# working.net
KiCad netlist of a schematic drawn in EAGLE
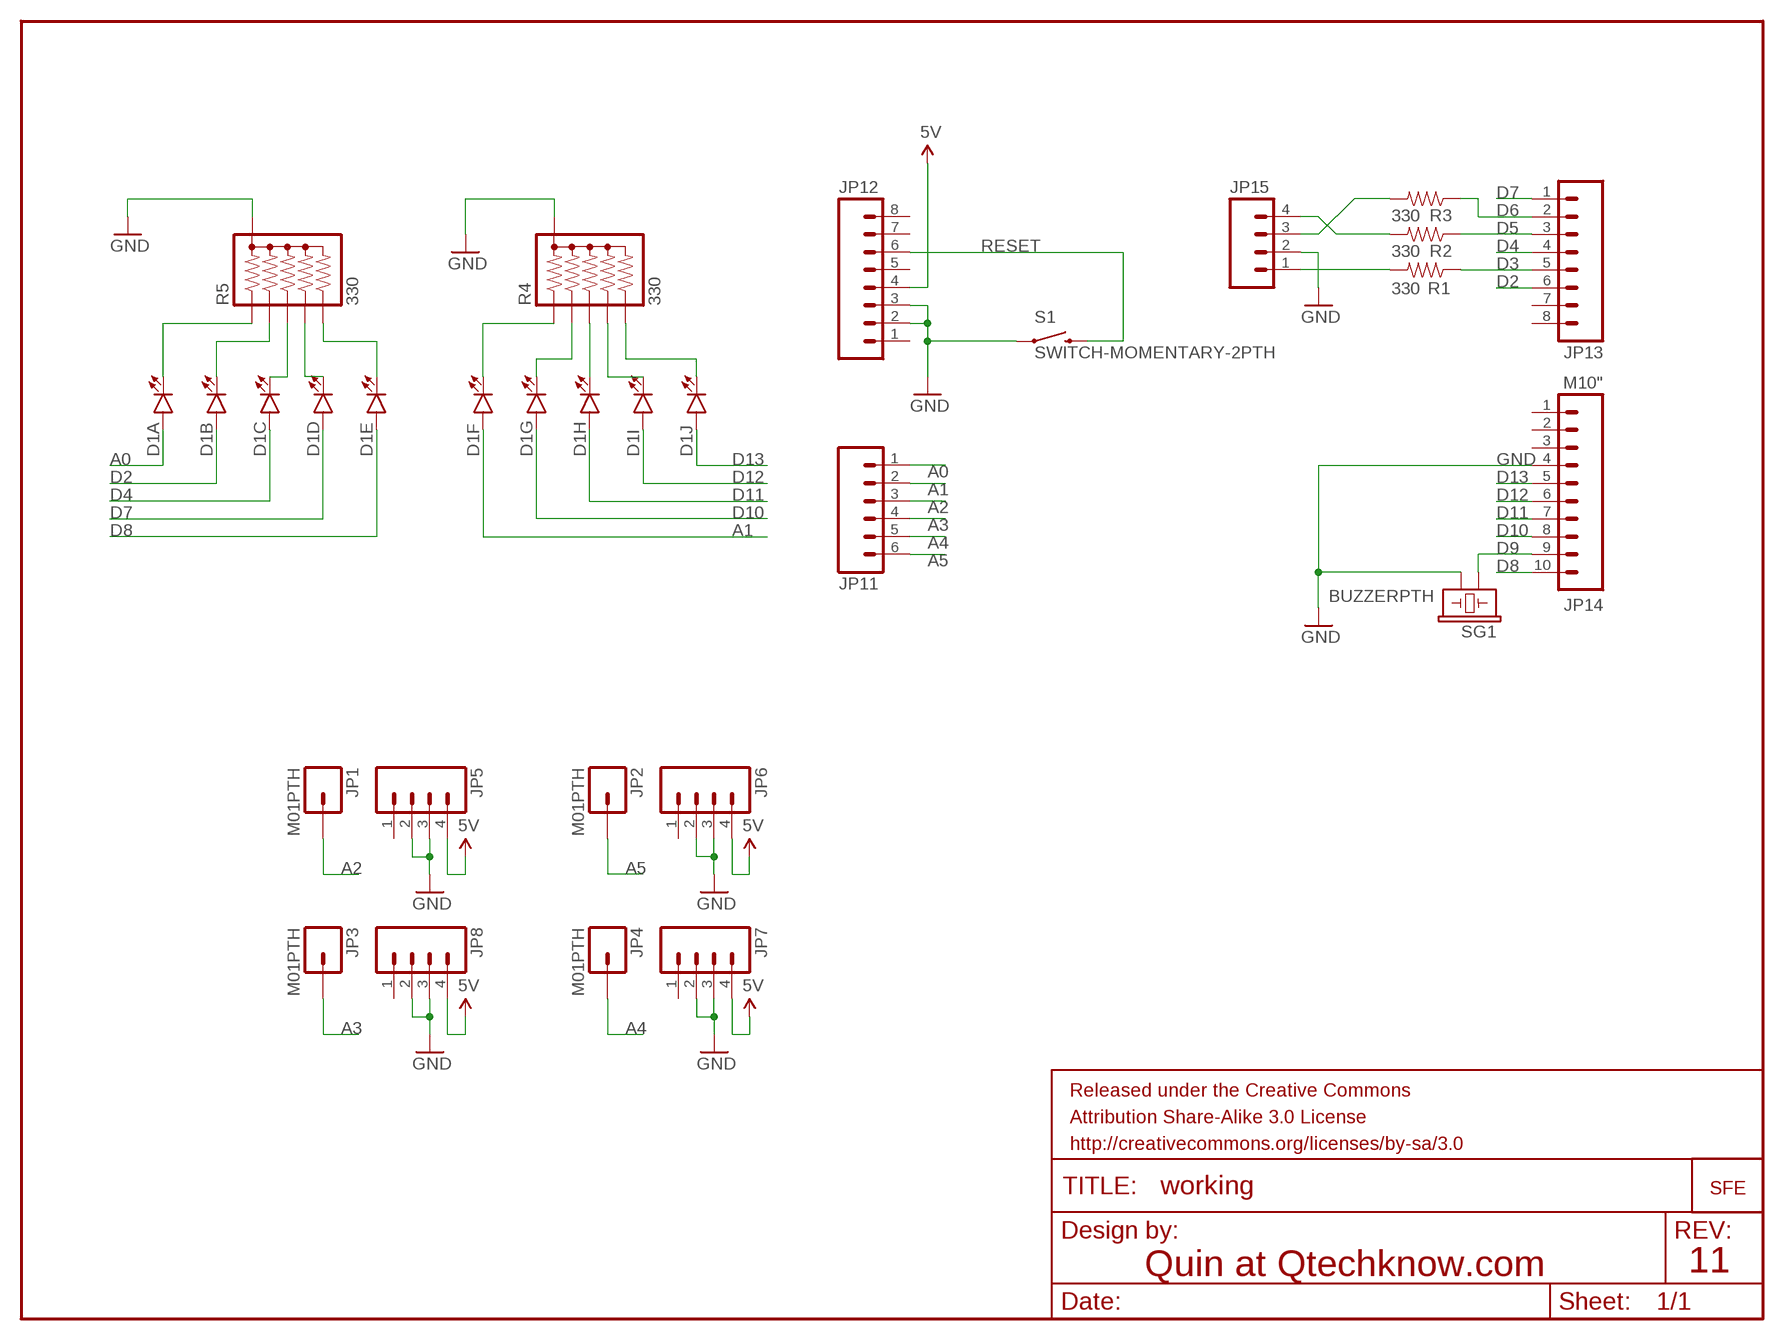
[diagram p0: schematic, sheet 1]

(export (version "E")
  (design (tool "Eeschema 10.0.6"))
  (components
    (comp (ref "D1")
      (value "LED_BARGRAPH_10")
      (footprint "eagle-import:LED_BARGAPH_10")
      (libsource (lib "eagle-import") (part "LED_BARGRAPH_10"))
    )
    (comp (ref "FRAME1")
      (value "FRAME-LETTER")
      (footprint "eagle-import:CREATIVE_COMMONS")
      (libsource (lib "eagle-import") (part "FRAME-LETTER"))
    )
    (comp (ref "JP1")
      (value "M01PTH")
      (footprint "eagle-import:1X01")
      (libsource (lib "eagle-import") (part "M01PTH"))
    )
    (comp (ref "JP2")
      (value "M01PTH")
      (footprint "eagle-import:1X01")
      (libsource (lib "eagle-import") (part "M01PTH"))
    )
    (comp (ref "JP3")
      (value "M01PTH")
      (footprint "eagle-import:1X01")
      (libsource (lib "eagle-import") (part "M01PTH"))
    )
    (comp (ref "JP4")
      (value "M01PTH")
      (footprint "eagle-import:1X01")
      (libsource (lib "eagle-import") (part "M01PTH"))
    )
    (comp (ref "JP5")
      (value "M04PTH")
      (footprint "eagle-import:1X04")
      (libsource (lib "eagle-import") (part "M04PTH"))
    )
    (comp (ref "JP6")
      (value "M04PTH")
      (footprint "eagle-import:1X04")
      (libsource (lib "eagle-import") (part "M04PTH"))
    )
    (comp (ref "JP7")
      (value "M04PTH")
      (footprint "eagle-import:1X04")
      (libsource (lib "eagle-import") (part "M04PTH"))
    )
    (comp (ref "JP8")
      (value "M04PTH")
      (footprint "eagle-import:1X04")
      (libsource (lib "eagle-import") (part "M04PTH"))
    )
    (comp (ref "JP9")
      (value "LOGO-SFENEW")
      (footprint "eagle-import:SFE-NEW-WEBLOGO")
      (libsource (lib "eagle-import") (part "LOGO-SFENEW"))
    )
    (comp (ref "JP11")
      (value "M06SIP")
      (footprint "eagle-import:1X06")
      (libsource (lib "eagle-import") (part "M06SIP"))
    )
    (comp (ref "JP12")
      (value "M081X08")
      (footprint "eagle-import:1X08")
      (libsource (lib "eagle-import") (part "M081X08"))
    )
    (comp (ref "JP13")
      (value "M081X08")
      (footprint "eagle-import:1X08")
      (libsource (lib "eagle-import") (part "M081X08"))
    )
    (comp (ref "JP14")
      (value "M10\"")
      (footprint "eagle-import:1X10")
      (libsource (lib "eagle-import") (part "M10{dblquote}"))
    )
    (comp (ref "JP15")
      (value "M04PTH")
      (footprint "eagle-import:1X04")
      (libsource (lib "eagle-import") (part "M04PTH"))
    )
    (comp (ref "R1")
      (value "330")
      (footprint "eagle-import:1_6W-RES")
      (libsource (lib "eagle-import") (part "RESISTORPTH-1/6W"))
    )
    (comp (ref "R2")
      (value "330")
      (footprint "eagle-import:1_6W-RES")
      (libsource (lib "eagle-import") (part "RESISTORPTH-1/6W"))
    )
    (comp (ref "R3")
      (value "330")
      (footprint "eagle-import:1_6W-RES")
      (libsource (lib "eagle-import") (part "RESISTORPTH-1/6W"))
    )
    (comp (ref "R4")
      (value "330")
      (footprint "eagle-import:RPACK-SIP-PTH-5")
      (libsource (lib "eagle-import") (part "RPACK-BUSSED-SIP-PTH-5"))
    )
    (comp (ref "R5")
      (value "330")
      (footprint "eagle-import:RPACK-SIP-PTH-5")
      (libsource (lib "eagle-import") (part "RPACK-BUSSED-SIP-PTH-5"))
    )
    (comp (ref "S1")
      (value "SWITCH-MOMENTARY-2PTH")
      (footprint "eagle-import:TACTILE-PTH")
      (libsource (lib "eagle-import") (part "SWITCH-MOMENTARY-2PTH"))
    )
    (comp (ref "SG1")
      (value "BUZZERPTH")
      (footprint "eagle-import:BUZZER-12MM")
      (libsource (lib "eagle-import") (part "BUZZERPTH"))
    )
  )
  (nets
    (net (code "1") (name "/A0") (class "Default")
      (node (ref "D1") (pin "1") (pinfunction "A_1") (pintype "passive"))
      (node (ref "JP11") (pin "1") (pinfunction "1_1") (pintype "passive"))
    )
    (net (code "2") (name "/A1") (class "Default")
      (node (ref "D1") (pin "6") (pinfunction "A_6") (pintype "passive"))
      (node (ref "JP11") (pin "2") (pinfunction "2_2") (pintype "passive"))
    )
    (net (code "3") (name "/A2") (class "Default")
      (node (ref "JP1") (pin "1") (pinfunction "1_1") (pintype "passive"))
      (node (ref "JP11") (pin "3") (pinfunction "3_3") (pintype "passive"))
    )
    (net (code "4") (name "/A3") (class "Default")
      (node (ref "JP11") (pin "4") (pinfunction "4_4") (pintype "passive"))
      (node (ref "JP3") (pin "1") (pinfunction "1_1") (pintype "passive"))
    )
    (net (code "5") (name "/A4") (class "Default")
      (node (ref "JP11") (pin "5") (pinfunction "5_5") (pintype "passive"))
      (node (ref "JP4") (pin "1") (pinfunction "1_1") (pintype "passive"))
    )
    (net (code "6") (name "/A5") (class "Default")
      (node (ref "JP11") (pin "6") (pinfunction "6_6") (pintype "passive"))
      (node (ref "JP2") (pin "1") (pinfunction "1_1") (pintype "passive"))
    )
    (net (code "7") (name "/D2") (class "Default")
      (node (ref "D1") (pin "2") (pinfunction "A_2") (pintype "passive"))
      (node (ref "JP13") (pin "6") (pinfunction "6_6") (pintype "passive"))
    )
    (net (code "8") (name "/D3") (class "Default")
      (node (ref "JP13") (pin "5") (pinfunction "5_5") (pintype "passive"))
      (node (ref "R1") (pin "1") (pinfunction "1_1") (pintype "passive"))
    )
    (net (code "9") (name "/D4") (class "Default")
      (node (ref "D1") (pin "3") (pinfunction "A_3") (pintype "passive"))
      (node (ref "JP13") (pin "4") (pinfunction "4_4") (pintype "passive"))
    )
    (net (code "10") (name "/D5") (class "Default")
      (node (ref "JP13") (pin "3") (pinfunction "3_3") (pintype "passive"))
      (node (ref "R2") (pin "1") (pinfunction "1_1") (pintype "passive"))
    )
    (net (code "11") (name "/D6") (class "Default")
      (node (ref "JP13") (pin "2") (pinfunction "2_2") (pintype "passive"))
      (node (ref "R3") (pin "1") (pinfunction "1_1") (pintype "passive"))
    )
    (net (code "12") (name "/D7") (class "Default")
      (node (ref "D1") (pin "4") (pinfunction "A_4") (pintype "passive"))
      (node (ref "JP13") (pin "1") (pinfunction "1_1") (pintype "passive"))
    )
    (net (code "13") (name "/D8") (class "Default")
      (node (ref "D1") (pin "5") (pinfunction "A_5") (pintype "passive"))
      (node (ref "JP14") (pin "10") (pinfunction "10_10") (pintype "passive"))
    )
    (net (code "14") (name "/D9") (class "Default")
      (node (ref "JP14") (pin "9") (pinfunction "9_9") (pintype "passive"))
      (node (ref "SG1") (pin "+") (pinfunction "1_+") (pintype "passive"))
    )
    (net (code "15") (name "/D10") (class "Default")
      (node (ref "D1") (pin "7") (pinfunction "A_7") (pintype "passive"))
      (node (ref "JP14") (pin "8") (pinfunction "8_8") (pintype "passive"))
    )
    (net (code "16") (name "/D11") (class "Default")
      (node (ref "D1") (pin "8") (pinfunction "A_8") (pintype "passive"))
      (node (ref "JP14") (pin "7") (pinfunction "7_7") (pintype "passive"))
    )
    (net (code "17") (name "/D12") (class "Default")
      (node (ref "D1") (pin "9") (pinfunction "A_9") (pintype "passive"))
      (node (ref "JP14") (pin "6") (pinfunction "6_6") (pintype "passive"))
    )
    (net (code "18") (name "/D13") (class "Default")
      (node (ref "D1") (pin "10") (pinfunction "A_10") (pintype "passive"))
      (node (ref "JP14") (pin "5") (pinfunction "5_5") (pintype "passive"))
    )
    (net (code "19") (name "/RESET") (class "Default")
      (node (ref "JP12") (pin "6") (pinfunction "6_6") (pintype "passive"))
      (node (ref "S1") (pin "3") (pinfunction "2_3") (pintype "passive"))
    )
    (net (code "20") (name "5V") (class "Default")
      (node (ref "JP12") (pin "4") (pinfunction "4_4") (pintype "passive"))
      (node (ref "JP5") (pin "4") (pinfunction "4_4") (pintype "passive"))
      (node (ref "JP6") (pin "4") (pinfunction "4_4") (pintype "passive"))
      (node (ref "JP7") (pin "4") (pinfunction "4_4") (pintype "passive"))
      (node (ref "JP8") (pin "4") (pinfunction "4_4") (pintype "passive"))
    )
    (net (code "21") (name "GND") (class "Default")
      (node (ref "JP12") (pin "2") (pinfunction "2_2") (pintype "passive"))
      (node (ref "JP12") (pin "3") (pinfunction "3_3") (pintype "passive"))
      (node (ref "JP14") (pin "4") (pinfunction "4_4") (pintype "passive"))
      (node (ref "JP15") (pin "2") (pinfunction "2_2") (pintype "passive"))
      (node (ref "JP5") (pin "2") (pinfunction "2_2") (pintype "passive"))
      (node (ref "JP5") (pin "3") (pinfunction "3_3") (pintype "passive"))
      (node (ref "JP6") (pin "2") (pinfunction "2_2") (pintype "passive"))
      (node (ref "JP6") (pin "3") (pinfunction "3_3") (pintype "passive"))
      (node (ref "JP7") (pin "2") (pinfunction "2_2") (pintype "passive"))
      (node (ref "JP7") (pin "3") (pinfunction "3_3") (pintype "passive"))
      (node (ref "JP8") (pin "2") (pinfunction "2_2") (pintype "passive"))
      (node (ref "JP8") (pin "3") (pinfunction "3_3") (pintype "passive"))
      (node (ref "R4") (pin "P$1") (pinfunction "1_P$1") (pintype "passive"))
      (node (ref "R5") (pin "P$1") (pinfunction "1_P$1") (pintype "passive"))
      (node (ref "S1") (pin "1") (pinfunction "1_1") (pintype "passive"))
      (node (ref "SG1") (pin "-") (pinfunction "2_-") (pintype "passive"))
    )
    (net (code "22") (name "Net-(D1A-C)") (class "Default")
      (node (ref "D1") (pin "20") (pinfunction "C_20") (pintype "passive"))
      (node (ref "R5") (pin "P$2") (pinfunction "2_P$2") (pintype "passive"))
    )
    (net (code "23") (name "Net-(D1B-C)") (class "Default")
      (node (ref "D1") (pin "19") (pinfunction "C_19") (pintype "passive"))
      (node (ref "R5") (pin "P$3") (pinfunction "3_P$3") (pintype "passive"))
    )
    (net (code "24") (name "Net-(D1C-C)") (class "Default")
      (node (ref "D1") (pin "18") (pinfunction "C_18") (pintype "passive"))
      (node (ref "R5") (pin "P$4") (pinfunction "4_P$4") (pintype "passive"))
    )
    (net (code "25") (name "Net-(D1D-C)") (class "Default")
      (node (ref "D1") (pin "17") (pinfunction "C_17") (pintype "passive"))
      (node (ref "R5") (pin "P$5") (pinfunction "5_P$5") (pintype "passive"))
    )
    (net (code "26") (name "Net-(D1E-C)") (class "Default")
      (node (ref "D1") (pin "16") (pinfunction "C_16") (pintype "passive"))
      (node (ref "R5") (pin "P$6") (pinfunction "6_P$6") (pintype "passive"))
    )
    (net (code "27") (name "Net-(D1F-C)") (class "Default")
      (node (ref "D1") (pin "15") (pinfunction "C_15") (pintype "passive"))
      (node (ref "R4") (pin "P$2") (pinfunction "2_P$2") (pintype "passive"))
    )
    (net (code "28") (name "Net-(D1G-C)") (class "Default")
      (node (ref "D1") (pin "14") (pinfunction "C_14") (pintype "passive"))
      (node (ref "R4") (pin "P$3") (pinfunction "3_P$3") (pintype "passive"))
    )
    (net (code "29") (name "Net-(D1H-C)") (class "Default")
      (node (ref "D1") (pin "13") (pinfunction "C_13") (pintype "passive"))
      (node (ref "R4") (pin "P$4") (pinfunction "4_P$4") (pintype "passive"))
    )
    (net (code "30") (name "Net-(D1I-C)") (class "Default")
      (node (ref "D1") (pin "12") (pinfunction "C_12") (pintype "passive"))
      (node (ref "R4") (pin "P$5") (pinfunction "5_P$5") (pintype "passive"))
    )
    (net (code "31") (name "Net-(D1J-C)") (class "Default")
      (node (ref "D1") (pin "11") (pinfunction "C_11") (pintype "passive"))
      (node (ref "R4") (pin "P$6") (pinfunction "6_P$6") (pintype "passive"))
    )
    (net (code "32") (name "Net-(JP15-Pad1)") (class "Default")
      (node (ref "JP15") (pin "1") (pinfunction "1_1") (pintype "passive"))
      (node (ref "R1") (pin "2") (pinfunction "2_2") (pintype "passive"))
    )
    (net (code "33") (name "Net-(JP15-Pad3)") (class "Default")
      (node (ref "JP15") (pin "3") (pinfunction "3_3") (pintype "passive"))
      (node (ref "R3") (pin "2") (pinfunction "2_2") (pintype "passive"))
    )
    (net (code "34") (name "Net-(JP15-Pad4)") (class "Default")
      (node (ref "JP15") (pin "4") (pinfunction "4_4") (pintype "passive"))
      (node (ref "R2") (pin "2") (pinfunction "2_2") (pintype "passive"))
    )
    (net (code "35") (name "unconnected-(JP5-Pad1)") (class "Default")
      (node (ref "JP5") (pin "1") (pinfunction "1_1") (pintype "passive"))
    )
    (net (code "36") (name "unconnected-(JP6-Pad1)") (class "Default")
      (node (ref "JP6") (pin "1") (pinfunction "1_1") (pintype "passive"))
    )
    (net (code "37") (name "unconnected-(JP7-Pad1)") (class "Default")
      (node (ref "JP7") (pin "1") (pinfunction "1_1") (pintype "passive"))
    )
    (net (code "38") (name "unconnected-(JP8-Pad1)") (class "Default")
      (node (ref "JP8") (pin "1") (pinfunction "1_1") (pintype "passive"))
    )
    (net (code "39") (name "unconnected-(JP12-Pad1)") (class "Default")
      (node (ref "JP12") (pin "1") (pinfunction "1_1") (pintype "passive"))
    )
    (net (code "40") (name "unconnected-(JP12-Pad5)") (class "Default")
      (node (ref "JP12") (pin "5") (pinfunction "5_5") (pintype "passive"))
    )
    (net (code "41") (name "unconnected-(JP12-Pad7)") (class "Default")
      (node (ref "JP12") (pin "7") (pinfunction "7_7") (pintype "passive"))
    )
    (net (code "42") (name "unconnected-(JP12-Pad8)") (class "Default")
      (node (ref "JP12") (pin "8") (pinfunction "8_8") (pintype "passive"))
    )
    (net (code "43") (name "unconnected-(JP13-Pad7)") (class "Default")
      (node (ref "JP13") (pin "7") (pinfunction "7_7") (pintype "passive"))
    )
    (net (code "44") (name "unconnected-(JP13-Pad8)") (class "Default")
      (node (ref "JP13") (pin "8") (pinfunction "8_8") (pintype "passive"))
    )
    (net (code "45") (name "unconnected-(JP14-Pad1)") (class "Default")
      (node (ref "JP14") (pin "1") (pinfunction "1_1") (pintype "passive"))
    )
    (net (code "46") (name "unconnected-(JP14-Pad2)") (class "Default")
      (node (ref "JP14") (pin "2") (pinfunction "2_2") (pintype "passive"))
    )
    (net (code "47") (name "unconnected-(JP14-Pad3)") (class "Default")
      (node (ref "JP14") (pin "3") (pinfunction "3_3") (pintype "passive"))
    )
  )
)
